# 5v_AC_DC.net
KiCad netlist of a schematic drawn in EAGLE
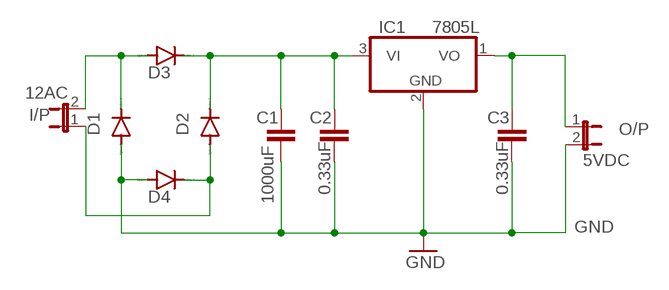
[diagram p0: schematic, sheet 1]

(export (version "E")
  (design (tool "Eeschema 10.0.6"))
  (components
    (comp (ref "C1")
      (value "1000uF")
      (footprint "eagle-import:C2.5-3")
      (libsource (lib "eagle-import") (part "C2,5-3"))
    )
    (comp (ref "C2")
      (value "0.33uF")
      (footprint "eagle-import:C2.5-3")
      (libsource (lib "eagle-import") (part "C2,5-3"))
    )
    (comp (ref "C3")
      (value "0.33uF")
      (footprint "eagle-import:C2.5-3")
      (libsource (lib "eagle-import") (part "C2,5-3"))
    )
    (comp (ref "D1")
      (value "1N4004")
      (footprint "eagle-import:DO41-10")
      (libsource (lib "eagle-import") (part "1N4004"))
    )
    (comp (ref "D2")
      (value "1N4004")
      (footprint "eagle-import:DO41-10")
      (libsource (lib "eagle-import") (part "1N4004"))
    )
    (comp (ref "D3")
      (value "1N4004")
      (footprint "eagle-import:DO41-10")
      (libsource (lib "eagle-import") (part "1N4004"))
    )
    (comp (ref "D4")
      (value "1N4004")
      (footprint "eagle-import:DO41-10")
      (libsource (lib "eagle-import") (part "1N4004"))
    )
    (comp (ref "I/P")
      (value "12AC")
      (footprint "eagle-import:JP1")
      (libsource (lib "eagle-import") (part "JP1E"))
    )
    (comp (ref "IC1")
      (value "7805L")
      (footprint "eagle-import:TO92")
      (libsource (lib "eagle-import") (part "78L05"))
    )
    (comp (ref "O/P")
      (value "5VDC")
      (footprint "eagle-import:JP1")
      (libsource (lib "eagle-import") (part "JP1E"))
    )
  )
  (nets
    (net (code "1") (name "GND") (class "Default")
      (node (ref "C1") (pin "2") (pinfunction "2_2") (pintype "passive"))
      (node (ref "C2") (pin "2") (pinfunction "2_2") (pintype "passive"))
      (node (ref "C3") (pin "2") (pinfunction "2_2") (pintype "passive"))
      (node (ref "D1") (pin "A") (pinfunction "A_A") (pintype "passive"))
      (node (ref "D4") (pin "A") (pinfunction "A_A") (pintype "passive"))
      (node (ref "IC1") (pin "2") (pinfunction "GND_2") (pintype "passive"))
      (node (ref "O/P") (pin "2") (pinfunction "2_2") (pintype "passive"))
    )
    (net (code "2") (name "Net-(D1-PadC)") (class "Default")
      (node (ref "D1") (pin "C") (pinfunction "C_C") (pintype "passive"))
      (node (ref "D3") (pin "A") (pinfunction "A_A") (pintype "passive"))
      (node (ref "I/P") (pin "2") (pinfunction "2_2") (pintype "passive"))
    )
    (net (code "3") (name "Net-(D2-PadA)") (class "Default")
      (node (ref "D2") (pin "A") (pinfunction "A_A") (pintype "passive"))
      (node (ref "D4") (pin "C") (pinfunction "C_C") (pintype "passive"))
      (node (ref "I/P") (pin "1") (pinfunction "1_1") (pintype "passive"))
    )
    (net (code "4") (name "Net-(IC1-VI)") (class "Default")
      (node (ref "C1") (pin "1") (pinfunction "1_1") (pintype "passive"))
      (node (ref "C2") (pin "1") (pinfunction "1_1") (pintype "passive"))
      (node (ref "D2") (pin "C") (pinfunction "C_C") (pintype "passive"))
      (node (ref "D3") (pin "C") (pinfunction "C_C") (pintype "passive"))
      (node (ref "IC1") (pin "3") (pinfunction "VI_3") (pintype "input"))
    )
    (net (code "5") (name "Net-(IC1-VO)") (class "Default")
      (node (ref "C3") (pin "1") (pinfunction "1_1") (pintype "passive"))
      (node (ref "IC1") (pin "1") (pinfunction "VO_1") (pintype "passive"))
      (node (ref "O/P") (pin "1") (pinfunction "1_1") (pintype "passive"))
    )
  )
)
